# power.net
KiCad netlist of a schematic drawn in Altium Designer
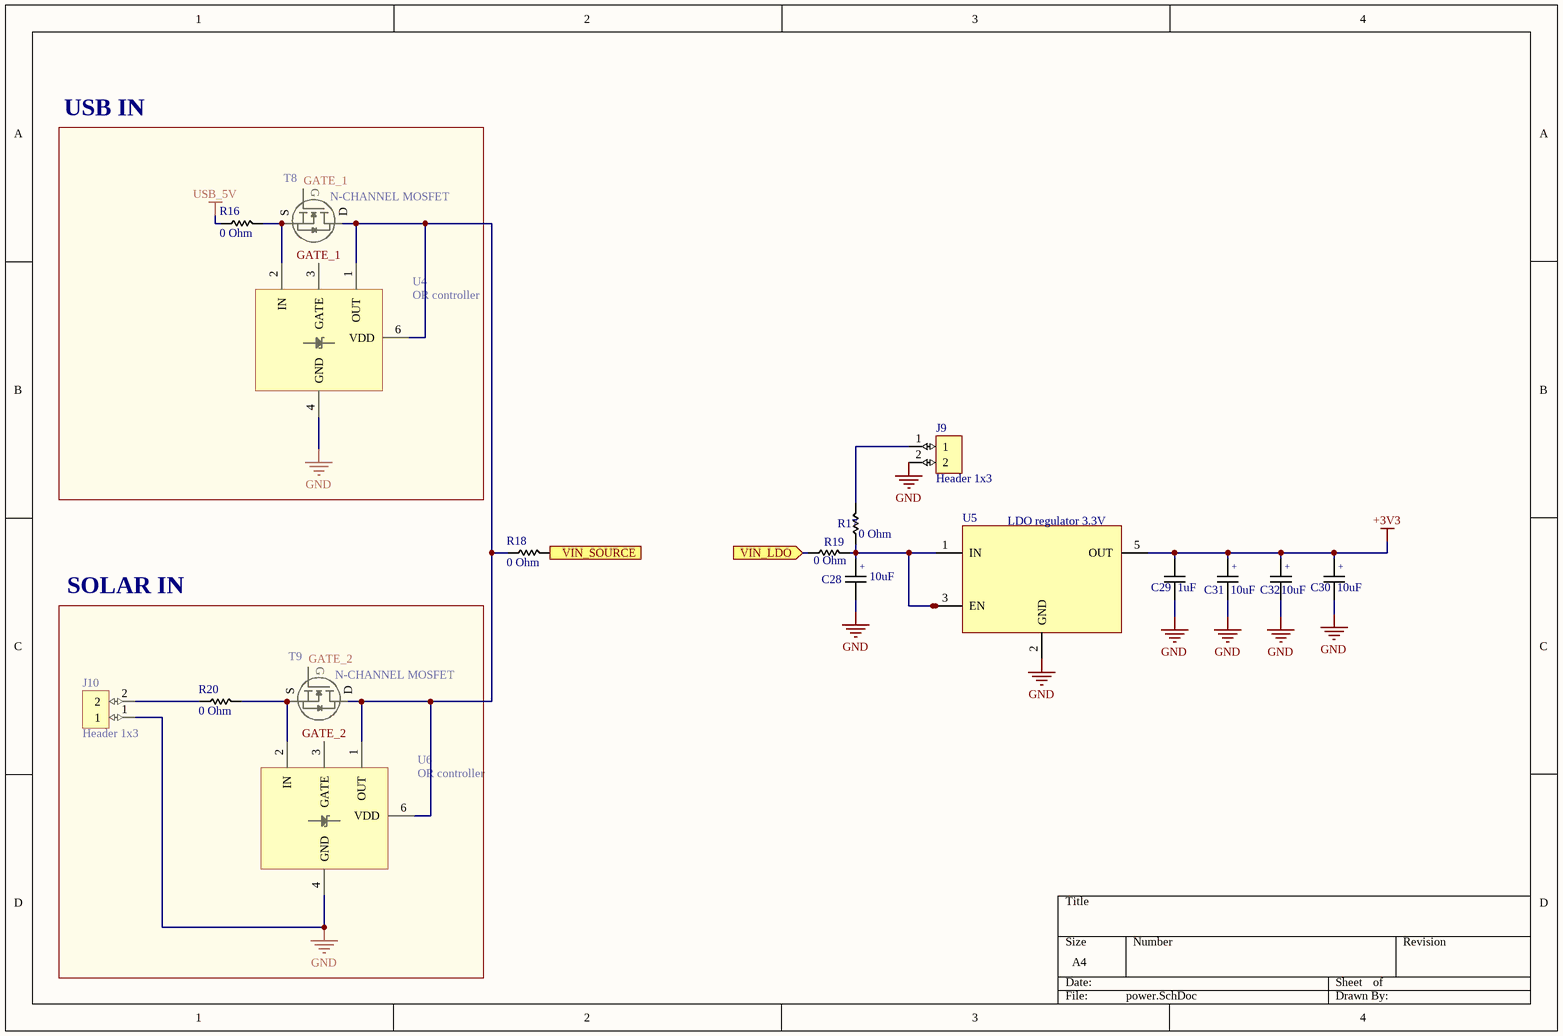
[diagram p0: power.SchDoc]

(export (version "E")
  (design (tool "Eeschema 10.0.6"))
  (components
    (comp (ref "C28")
      (value "10uF")
      (footprint "Capacitor electrolytic SMD 4x5.4")
      (fields (field (name "Comment") "El. Capacitor SMD 4x5.4"))
      (libsource (lib "Passive components") (part "El. Capacitor SMD 4x5.4"))
    )
    (comp (ref "C29")
      (value "1uF")
      (footprint "C0603")
      (fields (field (name "Comment") "Capacitor 0603"))
      (libsource (lib "Passive components") (part "Capacitor 0603"))
    )
    (comp (ref "C30")
      (value "10uF")
      (footprint "Capacitor electrolytic SMD 4x5.4")
      (fields (field (name "Comment") "El. Capacitor SMD 4x5.4"))
      (libsource (lib "") (part "El. Capacitor SMD 4x5.4_1"))
    )
    (comp (ref "C31")
      (value "10uF")
      (footprint "Capacitor electrolytic SMD 4x5.4")
      (fields (field (name "Comment") "El. Capacitor SMD 4x5.4"))
      (libsource (lib "Passive components") (part "El. Capacitor SMD 4x5.4"))
    )
    (comp (ref "C32")
      (value "10uF")
      (footprint "Capacitor electrolytic SMD 4x5.4")
      (fields (field (name "Comment") "El. Capacitor SMD 4x5.4"))
      (libsource (lib "Passive components") (part "El. Capacitor SMD 4x5.4"))
    )
    (comp (ref "J9")
      (value "Header 1x3")
      (footprint "HEADER 1X2 MALE JST")
      (libsource (lib "") (part "Header 1x2 Male_1"))
    )
    (comp (ref "J10")
      (value "Header 1x3")
      (footprint "Header 1x2 Male")
      (libsource (lib "Connectors") (part "Header 1x2 Male"))
    )
    (comp (ref "R16")
      (value "0 Ohm")
      (footprint "R0603")
      (fields (field (name "Comment") "Resistor 0603"))
      (libsource (lib "Passive components") (part "Resistor 0603"))
    )
    (comp (ref "R17")
      (value "0 Ohm")
      (footprint "R0603")
      (fields (field (name "Comment") "Resistor 0603"))
      (libsource (lib "Passive components") (part "Resistor 0603"))
    )
    (comp (ref "R18")
      (value "0 Ohm")
      (footprint "R0603")
      (fields (field (name "Comment") "Resistor 0603"))
      (libsource (lib "Passive components") (part "Resistor 0603"))
    )
    (comp (ref "R19")
      (value "0 Ohm")
      (footprint "R0603")
      (fields (field (name "Comment") "Resistor 0603"))
      (libsource (lib "Passive components") (part "Resistor 0603"))
    )
    (comp (ref "R20")
      (value "0 Ohm")
      (footprint "R0603")
      (fields (field (name "Comment") "Resistor 0603"))
      (libsource (lib "Passive components") (part "Resistor 0603"))
    )
    (comp (ref "T8")
      (value "N-CHANNEL MOSFET")
      (footprint "N-CHANNEL MOSFET")
      (libsource (lib "Transistors") (part "N-CHANNEL MOSFET"))
    )
    (comp (ref "T9")
      (value "N-CHANNEL MOSFET")
      (footprint "N-CHANNEL MOSFET")
      (libsource (lib "Transistors") (part "N-CHANNEL MOSFET"))
    )
    (comp (ref "U4")
      (value "OR controller")
      (footprint "IC:DFN 6-pins")
      (description "LTC4357")
      (libsource (lib "IC") (part "OR controller"))
    )
    (comp (ref "U5")
      (value "LDO regulator 3.3V")
      (footprint "LDO 5-pin SOT")
      (libsource (lib "IC") (part "TLV700 - 3.3V"))
    )
    (comp (ref "U6")
      (value "OR controller")
      (footprint "IC:DFN 6-pins")
      (description "LTC4357")
      (libsource (lib "IC") (part "OR controller"))
    )
  )
  (nets
    (net (code "1") (name "+3V3") (class "Default")
      (node (ref "C29") (pin "2") (pinfunction "2_2") (pintype "passive"))
      (node (ref "C30") (pin "1") (pinfunction "1_1") (pintype "passive"))
      (node (ref "C31") (pin "1") (pinfunction "1_1") (pintype "passive"))
      (node (ref "C32") (pin "1") (pinfunction "1_1") (pintype "passive"))
      (node (ref "U5") (pin "5") (pinfunction "OUT_5") (pintype "passive"))
    )
    (net (code "2") (name "/GATE_1") (class "Default")
      (node (ref "T8") (pin "1") (pinfunction "G_1") (pintype "passive"))
      (node (ref "U4") (pin "3") (pinfunction "GATE_3") (pintype "passive"))
    )
    (net (code "3") (name "/GATE_2") (class "Default")
      (node (ref "T9") (pin "1") (pinfunction "G_1") (pintype "passive"))
      (node (ref "U6") (pin "3") (pinfunction "GATE_3") (pintype "passive"))
    )
    (net (code "4") (name "/VIN_LDO") (class "Default")
      (node (ref "R19") (pin "1") (pinfunction "1_1") (pintype "passive"))
    )
    (net (code "5") (name "/VIN_SOURCE") (class "Default")
      (node (ref "R18") (pin "2") (pinfunction "2_2") (pintype "passive"))
    )
    (net (code "6") (name "GND") (class "Default")
      (node (ref "C28") (pin "2") (pinfunction "2_2") (pintype "passive"))
      (node (ref "C29") (pin "1") (pinfunction "1_1") (pintype "passive"))
      (node (ref "C30") (pin "2") (pinfunction "2_2") (pintype "passive"))
      (node (ref "C31") (pin "2") (pinfunction "2_2") (pintype "passive"))
      (node (ref "C32") (pin "2") (pinfunction "2_2") (pintype "passive"))
      (node (ref "J10") (pin "1") (pinfunction "1_1") (pintype "bidirectional"))
      (node (ref "J9") (pin "2") (pinfunction "2_2") (pintype "bidirectional"))
      (node (ref "U4") (pin "4") (pinfunction "GND_4") (pintype "passive"))
      (node (ref "U5") (pin "2") (pinfunction "GND_2") (pintype "passive"))
      (node (ref "U6") (pin "4") (pinfunction "GND_4") (pintype "passive"))
    )
    (net (code "7") (name "Net-(J9-Pad1)") (class "Default")
      (node (ref "J9") (pin "1") (pinfunction "1_1") (pintype "bidirectional"))
      (node (ref "R17") (pin "2") (pinfunction "2_2") (pintype "passive"))
    )
    (net (code "8") (name "Net-(J10-Pad2)") (class "Default")
      (node (ref "J10") (pin "2") (pinfunction "2_2") (pintype "bidirectional"))
      (node (ref "R20") (pin "1") (pinfunction "1_1") (pintype "passive"))
    )
    (net (code "9") (name "Net-(T8-D)") (class "Default")
      (node (ref "R18") (pin "1") (pinfunction "1_1") (pintype "passive"))
      (node (ref "T8") (pin "3") (pinfunction "D_3") (pintype "passive"))
      (node (ref "T9") (pin "3") (pinfunction "D_3") (pintype "passive"))
      (node (ref "U4") (pin "1") (pinfunction "OUT_1") (pintype "passive"))
      (node (ref "U4") (pin "6") (pinfunction "VDD_6") (pintype "passive"))
      (node (ref "U6") (pin "1") (pinfunction "OUT_1") (pintype "passive"))
      (node (ref "U6") (pin "6") (pinfunction "VDD_6") (pintype "passive"))
    )
    (net (code "10") (name "Net-(T8-S)") (class "Default")
      (node (ref "R16") (pin "2") (pinfunction "2_2") (pintype "passive"))
      (node (ref "T8") (pin "2") (pinfunction "S_2") (pintype "passive"))
      (node (ref "U4") (pin "2") (pinfunction "IN_2") (pintype "passive"))
    )
    (net (code "11") (name "Net-(T9-S)") (class "Default")
      (node (ref "R20") (pin "2") (pinfunction "2_2") (pintype "passive"))
      (node (ref "T9") (pin "2") (pinfunction "S_2") (pintype "passive"))
      (node (ref "U6") (pin "2") (pinfunction "IN_2") (pintype "passive"))
    )
    (net (code "12") (name "Net-(U5-EN)") (class "Default")
      (node (ref "C28") (pin "1") (pinfunction "1_1") (pintype "passive"))
      (node (ref "R17") (pin "1") (pinfunction "1_1") (pintype "passive"))
      (node (ref "R19") (pin "2") (pinfunction "2_2") (pintype "passive"))
      (node (ref "U5") (pin "1") (pinfunction "IN_1") (pintype "passive"))
      (node (ref "U5") (pin "3") (pinfunction "EN_3") (pintype "passive"))
    )
    (net (code "13") (name "USB_5V") (class "Default")
      (node (ref "R16") (pin "1") (pinfunction "1_1") (pintype "passive"))
    )
    (net (code "14") (name "unconnected-(U4-Pad1)") (class "Default")
      (node (ref "U4") (pin "1") (pinfunction "1_1") (pintype "passive"))
    )
    (net (code "15") (name "unconnected-(U4-Pad2)") (class "Default")
      (node (ref "U4") (pin "2") (pinfunction "2_2") (pintype "passive"))
    )
    (net (code "16") (name "unconnected-(U6-Pad1)") (class "Default")
      (node (ref "U6") (pin "1") (pinfunction "1_1") (pintype "passive"))
    )
    (net (code "17") (name "unconnected-(U6-Pad2)") (class "Default")
      (node (ref "U6") (pin "2") (pinfunction "2_2") (pintype "passive"))
    )
  )
)
